# PSU.net
KiCad netlist of a schematic drawn in Altium Designer
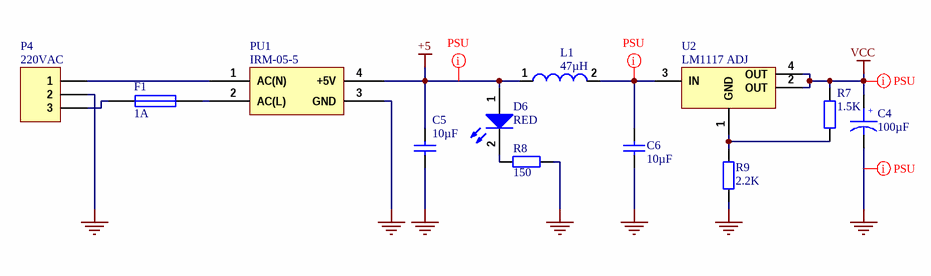
[diagram p0: PSU.SchDoc]

(export (version "E")
  (design (tool "Eeschema 10.0.6"))
  (components
    (comp (ref "C4")
      (value "100µF")
      (footprint "Kemet_63")
      (description "SMD Polarized Capacitor 16V")
      (fields
        (field (name "MANUFACTURER") "EPCOS")
        (field (name "MANUFACTURER PART NUMBER") "B41142A4107M")
        (field (name "HAUTEUR") "7.7")
        (field (name "LONGUEUR/HAUTEUR") "7.7")
      )
      (libsource (lib "BRA") (part "Cap Pol 100µF - 16"))
    )
    (comp (ref "C5")
      (value "10µF")
      (footprint "C 0805(2012)x0.65")
      (description "Capacitor non polarized 10µF SMD 0805")
      (fields (field (name "TOLERANCE") "10%") (field (name "VOLTAGE") "16V"))
      (libsource (lib "BRA") (part "Cap 0805 10µF"))
    )
    (comp (ref "C6")
      (value "10µF")
      (footprint "C 0805(2012)x0.65")
      (description "Capacitor non polarized 10µF SMD 0805")
      (fields (field (name "TOLERANCE") "10%") (field (name "VOLTAGE") "16V"))
      (libsource (lib "BRA") (part "Cap 0805 10µF"))
    )
    (comp (ref "D6")
      (value "RED")
      (footprint "0603-LEDR")
      (description "Surface Mount Chip LED, Red")
      (fields
        (field (name "MANUFACTURER") "AVAGO TECHNOLOGIES")
        (field (name "MANUFACTURER PART NUMBER") "HSMH-C190.")
        (field (name "LONGUEUR/HAUTEUR") "1.6")
      )
      (libsource (lib "BRA") (part "HSMH-C190"))
    )
    (comp (ref "F1")
      (value "1A")
      (footprint "FUS5X20")
      (description "Fuse holder 5x20 SMD")
      (fields
        (field (name "MANUFACTURER") "LITTELFUSE WICKMANN")
        (field (name "MANUFACTURER PART NUMBER") "65800001009")
      )
      (libsource (lib "BRA") (part "Fuse holder SMD 5X20"))
    )
    (comp (ref "L1")
      (value "47µH")
      (footprint "Self DO3316P")
      (fields
        (field (name "MANUFACTURER") "COILCRAFT")
        (field (name "MANUFACTURER PART NUMBER") "DO3316P-473MLD")
      )
      (libsource (lib "UTIL_Library") (part "SELF"))
    )
    (comp (ref "P4")
      (value "220VAC")
      (footprint "CO3P381 - RIGHT")
      (description "Header, 3-Pin")
      (fields (field (name "PUBLISHER") "Altium Limited"))
      (libsource (lib "Miscellaneous Connectors") (part "Header 3"))
    )
    (comp (ref "PU1")
      (value "IRM-05-5")
      (footprint "IRM-05-X.X")
      (description "POWER SUPPLY 5V 1A")
      (libsource (lib "BRA") (part "IRM-05-5"))
    )
    (comp (ref "R7")
      (value "1.5K")
      (footprint "R 0805(2012)")
      (description "Resistor SMD 0805 1.5K")
      (fields (field (name "TOLERANCE") "1%"))
      (libsource (lib "BRA") (part "Resistor 0805 1.5K"))
    )
    (comp (ref "R8")
      (value "150")
      (footprint "R 0805(2012)")
      (description "Resistor SMD 0805 150")
      (fields
        (field (name "MANUFACTURER") "YAGEO")
        (field (name "MANUFACTURER PART NUMBER") "RC0805JR-07150KL")
      )
      (libsource (lib "BRA") (part "Resistor 0805 150"))
    )
    (comp (ref "R9")
      (value "2.2K")
      (footprint "R 0805(2012)")
      (description "Resistor SMD 0805 2.2K")
      (fields
        (field (name "MANUFACTURER") "BOURNS")
        (field (name "MANUFACTURER PART NUMBER") "CR0805-FX-2201ELF")
      )
      (libsource (lib "BRA") (part "Resistor 0805 2.2K"))
    )
    (comp (ref "U2")
      (value "LM1117 ADJ")
      (footprint "SOT223")
      (description "800mA Adjustable low-Dropout Linear Regulator, 3-pin TO-252")
      (libsource (lib "BRA") (part "LM1117DT-ADJ"))
    )
  )
  (nets
    (net (code "1") (name "+5") (class "Default")
      (node (ref "C5") (pin "1") (pinfunction "1_1") (pintype "passive"))
      (node (ref "D6") (pin "1") (pinfunction "A_1") (pintype "passive"))
      (node (ref "L1") (pin "1") (pinfunction "1_1") (pintype "passive"))
      (node (ref "PU1") (pin "4") (pinfunction "+5V_4") (pintype "passive"))
    )
    (net (code "2") (name "GND") (class "Default")
      (node (ref "C4") (pin "2") (pinfunction "2_2") (pintype "passive"))
      (node (ref "C5") (pin "2") (pinfunction "2_2") (pintype "passive"))
      (node (ref "C6") (pin "2") (pinfunction "2_2") (pintype "passive"))
      (node (ref "P4") (pin "2") (pinfunction "2_2") (pintype "passive"))
      (node (ref "PU1") (pin "3") (pinfunction "GND_3") (pintype "passive"))
      (node (ref "R8") (pin "1") (pinfunction "1_1") (pintype "passive"))
      (node (ref "R9") (pin "1") (pinfunction "1_1") (pintype "passive"))
    )
    (net (code "3") (name "Net-(D6-K)") (class "Default")
      (node (ref "D6") (pin "2") (pinfunction "K_2") (pintype "passive"))
      (node (ref "R8") (pin "2") (pinfunction "2_2") (pintype "passive"))
    )
    (net (code "4") (name "Net-(F1-Pad2)") (class "Default")
      (node (ref "F1") (pin "2") (pinfunction "2_2") (pintype "passive"))
      (node (ref "P4") (pin "3") (pinfunction "3_3") (pintype "passive"))
    )
    (net (code "5") (name "Net-(PU1-AC(L))") (class "Default")
      (node (ref "F1") (pin "1") (pinfunction "1_1") (pintype "passive"))
      (node (ref "PU1") (pin "2") (pinfunction "AC(L)_2") (pintype "passive"))
    )
    (net (code "6") (name "Net-(PU1-AC(N))") (class "Default")
      (node (ref "P4") (pin "1") (pinfunction "1_1") (pintype "passive"))
      (node (ref "PU1") (pin "1") (pinfunction "AC(N)_1") (pintype "passive"))
    )
    (net (code "7") (name "Net-(U2-GND)") (class "Default")
      (node (ref "R7") (pin "1") (pinfunction "1_1") (pintype "passive"))
      (node (ref "R9") (pin "2") (pinfunction "2_2") (pintype "passive"))
      (node (ref "U2") (pin "1") (pinfunction "GND_1") (pintype "power_in"))
    )
    (net (code "8") (name "Net-(U2-IN)") (class "Default")
      (node (ref "C6") (pin "1") (pinfunction "1_1") (pintype "passive"))
      (node (ref "L1") (pin "2") (pinfunction "2_2") (pintype "passive"))
      (node (ref "U2") (pin "3") (pinfunction "IN_3") (pintype "power_in"))
    )
    (net (code "9") (name "VCC") (class "Default")
      (node (ref "C4") (pin "1") (pinfunction "1_1") (pintype "passive"))
      (node (ref "R7") (pin "2") (pinfunction "2_2") (pintype "passive"))
      (node (ref "U2") (pin "2") (pinfunction "OUT_2") (pintype "power_in"))
      (node (ref "U2") (pin "4") (pinfunction "OUT_4") (pintype "power_in"))
    )
  )
)
